# IPNS_v0_1_MCU.net
KiCad netlist of a schematic drawn in EAGLE
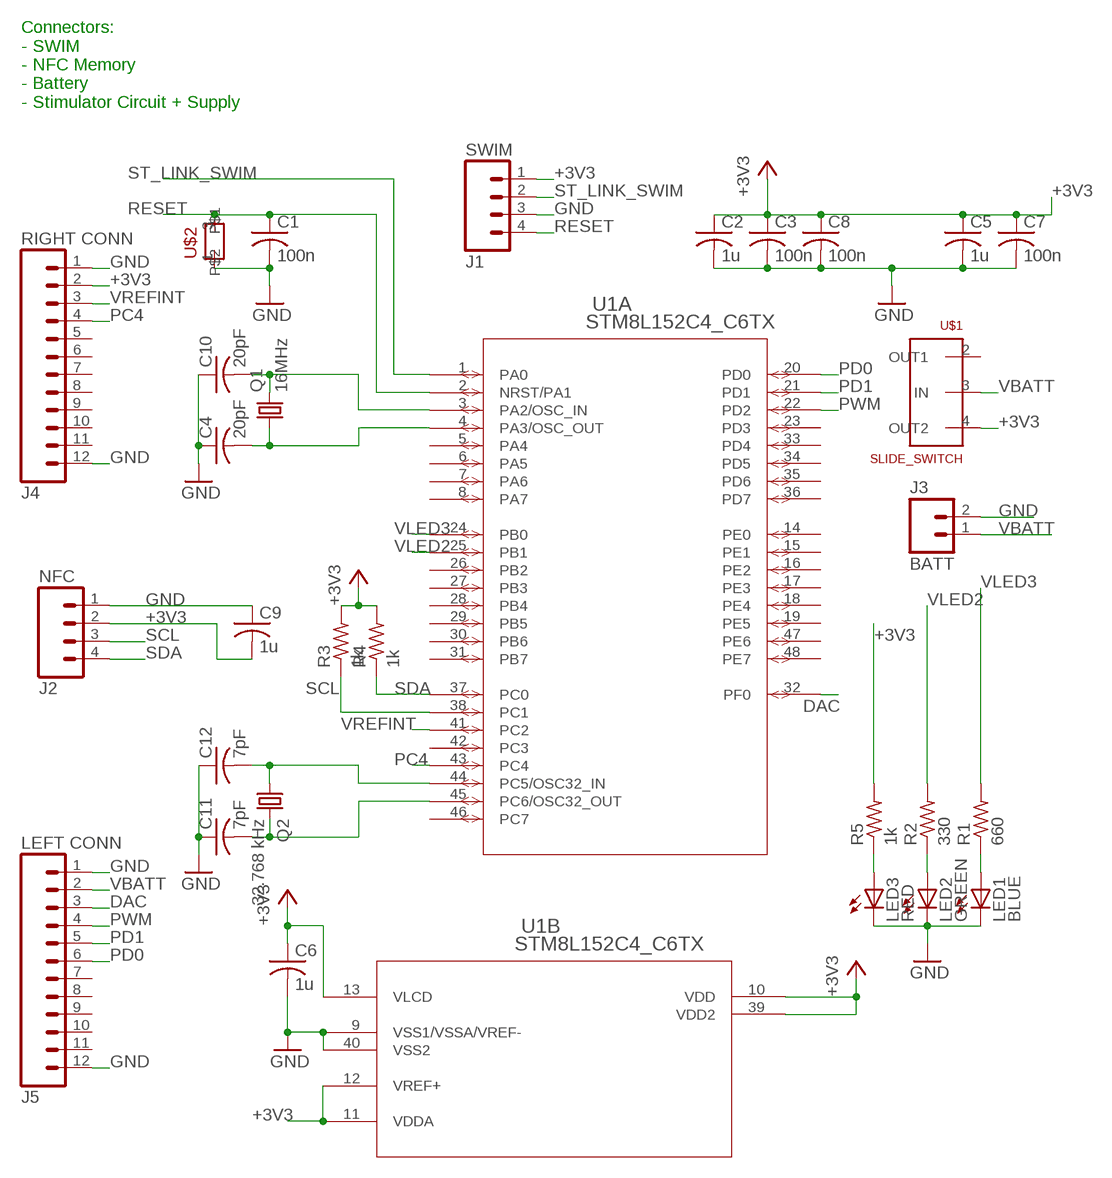
[diagram p0: schematic, sheet 1]

(export (version "E")
  (design (tool "Eeschema 10.0.6"))
  (components
    (comp (ref "C1")
      (value "100n")
      (footprint "eagle-import:C0805")
      (libsource (lib "eagle-import") (part "C-USC0805"))
    )
    (comp (ref "C2")
      (value "1u")
      (footprint "eagle-import:C0805")
      (libsource (lib "eagle-import") (part "C-USC0805"))
    )
    (comp (ref "C3")
      (value "100n")
      (footprint "eagle-import:C0805")
      (libsource (lib "eagle-import") (part "C-USC0805"))
    )
    (comp (ref "C4")
      (value "20pF")
      (footprint "eagle-import:C0805")
      (libsource (lib "eagle-import") (part "C-USC0805"))
    )
    (comp (ref "C5")
      (value "1u")
      (footprint "eagle-import:C0805")
      (libsource (lib "eagle-import") (part "C-USC0805"))
    )
    (comp (ref "C6")
      (value "1u")
      (footprint "eagle-import:C0805")
      (libsource (lib "eagle-import") (part "C-USC0805"))
    )
    (comp (ref "C7")
      (value "100n")
      (footprint "eagle-import:C0805")
      (libsource (lib "eagle-import") (part "C-USC0805"))
    )
    (comp (ref "C8")
      (value "100n")
      (footprint "eagle-import:C0805")
      (libsource (lib "eagle-import") (part "C-USC0805"))
    )
    (comp (ref "C9")
      (value "1u")
      (footprint "eagle-import:C0805")
      (libsource (lib "eagle-import") (part "C-USC0805"))
    )
    (comp (ref "C10")
      (value "20pF")
      (footprint "eagle-import:C0805")
      (libsource (lib "eagle-import") (part "C-USC0805"))
    )
    (comp (ref "C11")
      (value "7pF")
      (footprint "eagle-import:C0805")
      (libsource (lib "eagle-import") (part "C-USC0805"))
    )
    (comp (ref "C12")
      (value "7pF")
      (footprint "eagle-import:C0805")
      (libsource (lib "eagle-import") (part "C-USC0805"))
    )
    (comp (ref "J1")
      (value "SWIM")
      (footprint "eagle-import:1X04")
      (libsource (lib "eagle-import") (part "M04PTH"))
    )
    (comp (ref "J2")
      (value "NFC")
      (footprint "eagle-import:1X04")
      (libsource (lib "eagle-import") (part "M04PTH"))
    )
    (comp (ref "J3")
      (value "BATT")
      (footprint "eagle-import:1X02")
      (libsource (lib "eagle-import") (part "M02PTH"))
    )
    (comp (ref "J4")
      (value "RIGHT CONN")
      (footprint "eagle-import:1X12")
      (libsource (lib "eagle-import") (part "M12PTH"))
    )
    (comp (ref "J5")
      (value "LEFT CONN")
      (footprint "eagle-import:1X12")
      (libsource (lib "eagle-import") (part "M12PTH"))
    )
    (comp (ref "LED1")
      (value "BLUE")
      (footprint "eagle-import:CHIP-LED0805")
      (libsource (lib "eagle-import") (part "LEDCHIP-LED0805"))
    )
    (comp (ref "LED2")
      (value "GREEN")
      (footprint "eagle-import:CHIP-LED0805")
      (libsource (lib "eagle-import") (part "LEDCHIP-LED0805"))
    )
    (comp (ref "LED3")
      (value "RED")
      (footprint "eagle-import:CHIP-LED0805")
      (libsource (lib "eagle-import") (part "LEDCHIP-LED0805"))
    )
    (comp (ref "Q1")
      (value "16MHz")
      (footprint "eagle-import:HC49_S")
      (libsource (lib "eagle-import") (part "CRYSTALHC49S"))
    )
    (comp (ref "Q2")
      (value "32.768 kHz")
      (footprint "eagle-import:TC26H")
      (libsource (lib "eagle-import") (part "CRYSTALTC26H"))
    )
    (comp (ref "R1")
      (value "660")
      (footprint "eagle-import:R0805")
      (libsource (lib "eagle-import") (part "R-US_R0805"))
    )
    (comp (ref "R2")
      (value "330")
      (footprint "eagle-import:R0805")
      (libsource (lib "eagle-import") (part "R-US_R0805"))
    )
    (comp (ref "R3")
      (value "1k")
      (footprint "eagle-import:R0805")
      (libsource (lib "eagle-import") (part "R-US_R0805"))
    )
    (comp (ref "R4")
      (value "1k")
      (footprint "eagle-import:R0805")
      (libsource (lib "eagle-import") (part "R-US_R0805"))
    )
    (comp (ref "R5")
      (value "1k")
      (footprint "eagle-import:R0805")
      (libsource (lib "eagle-import") (part "R-US_R0805"))
    )
    (comp (ref "U$1")
      (value "SLIDE_SWITCH")
      (footprint "eagle-import:SLIDE_SWITCH")
      (libsource (lib "eagle-import") (part "SLIDE_SWITCH"))
    )
    (comp (ref "U$2")
      (value "PUSH-BUTTON")
      (footprint "eagle-import:PUSH-BUTTON")
      (libsource (lib "eagle-import") (part "PUSH-BUTTON"))
    )
    (comp (ref "U1")
      (value "STM8L152C4_C6TX")
      (footprint "eagle-import:LQFP48-7X7MM")
      (fields
        (field (name "MANUFACTURER_PART_NUMBER") "stm8l152c4_c6tx")
        (field (name "COPYRIGHT") "Copyright (C) 2016 Accelerated Designs. All rights reserved")
      )
      (libsource (lib "eagle-import") (part "STM8L152C4_C6TX"))
    )
  )
  (nets
    (net (code "1") (name "+3V3") (class "Default")
      (node (ref "C2") (pin "1") (pinfunction "1_1") (pintype "passive"))
      (node (ref "C3") (pin "1") (pinfunction "1_1") (pintype "passive"))
      (node (ref "C5") (pin "1") (pinfunction "1_1") (pintype "passive"))
      (node (ref "C6") (pin "1") (pinfunction "1_1") (pintype "passive"))
      (node (ref "C7") (pin "1") (pinfunction "1_1") (pintype "passive"))
      (node (ref "C8") (pin "1") (pinfunction "1_1") (pintype "passive"))
      (node (ref "C9") (pin "2") (pinfunction "2_2") (pintype "passive"))
      (node (ref "J1") (pin "1") (pinfunction "1_1") (pintype "passive"))
      (node (ref "J2") (pin "2") (pinfunction "2_2") (pintype "passive"))
      (node (ref "J4") (pin "2") (pinfunction "2_2") (pintype "passive"))
      (node (ref "R3") (pin "2") (pinfunction "2_2") (pintype "passive"))
      (node (ref "R4") (pin "2") (pinfunction "2_2") (pintype "passive"))
      (node (ref "R5") (pin "2") (pinfunction "2_2") (pintype "passive"))
      (node (ref "U$1") (pin "4") (pinfunction "OUT2_4") (pintype "bidirectional"))
      (node (ref "U1") (pin "10") (pinfunction "VDD_10") (pintype "power_in"))
      (node (ref "U1") (pin "11") (pinfunction "VDDA_11") (pintype "power_in"))
      (node (ref "U1") (pin "12") (pinfunction "VREF+_12") (pintype "power_in"))
      (node (ref "U1") (pin "13") (pinfunction "VLCD_13") (pintype "power_in"))
      (node (ref "U1") (pin "39") (pinfunction "VDD2_39") (pintype "power_in"))
    )
    (net (code "2") (name "/DAC") (class "Default")
      (node (ref "J5") (pin "3") (pinfunction "3_3") (pintype "passive"))
      (node (ref "U1") (pin "32") (pinfunction "PF0_32") (pintype "bidirectional"))
    )
    (net (code "3") (name "/PC4") (class "Default")
      (node (ref "J4") (pin "4") (pinfunction "4_4") (pintype "passive"))
      (node (ref "U1") (pin "43") (pinfunction "PC4_43") (pintype "bidirectional"))
    )
    (net (code "4") (name "/PD0") (class "Default")
      (node (ref "J5") (pin "6") (pinfunction "6_6") (pintype "passive"))
      (node (ref "U1") (pin "20") (pinfunction "PD0_20") (pintype "bidirectional"))
    )
    (net (code "5") (name "/PD1") (class "Default")
      (node (ref "J5") (pin "5") (pinfunction "5_5") (pintype "passive"))
      (node (ref "U1") (pin "21") (pinfunction "PD1_21") (pintype "bidirectional"))
    )
    (net (code "6") (name "/PWM") (class "Default")
      (node (ref "J5") (pin "4") (pinfunction "4_4") (pintype "passive"))
      (node (ref "U1") (pin "22") (pinfunction "PD2_22") (pintype "bidirectional"))
    )
    (net (code "7") (name "/RESET") (class "Default")
      (node (ref "C1") (pin "1") (pinfunction "1_1") (pintype "passive"))
      (node (ref "J1") (pin "4") (pinfunction "4_4") (pintype "passive"))
      (node (ref "U$2") (pin "3") (pinfunction "P$2_3") (pintype "bidirectional"))
      (node (ref "U1") (pin "2") (pinfunction "NRST/PA1_2") (pintype "bidirectional"))
    )
    (net (code "8") (name "/SCL") (class "Default")
      (node (ref "J2") (pin "3") (pinfunction "3_3") (pintype "passive"))
      (node (ref "R3") (pin "1") (pinfunction "1_1") (pintype "passive"))
      (node (ref "U1") (pin "38") (pinfunction "PC1_38") (pintype "bidirectional"))
    )
    (net (code "9") (name "/SDA") (class "Default")
      (node (ref "J2") (pin "4") (pinfunction "4_4") (pintype "passive"))
      (node (ref "R4") (pin "1") (pinfunction "1_1") (pintype "passive"))
      (node (ref "U1") (pin "37") (pinfunction "PC0_37") (pintype "bidirectional"))
    )
    (net (code "10") (name "/ST_LINK_SWIM") (class "Default")
      (node (ref "J1") (pin "2") (pinfunction "2_2") (pintype "passive"))
      (node (ref "U1") (pin "1") (pinfunction "PA0_1") (pintype "bidirectional"))
    )
    (net (code "11") (name "/VBATT") (class "Default")
      (node (ref "J3") (pin "1") (pinfunction "1_1") (pintype "passive"))
      (node (ref "J5") (pin "2") (pinfunction "2_2") (pintype "passive"))
      (node (ref "U$1") (pin "3") (pinfunction "IN_3") (pintype "bidirectional"))
    )
    (net (code "12") (name "/VLED2") (class "Default")
      (node (ref "R2") (pin "2") (pinfunction "2_2") (pintype "passive"))
      (node (ref "U1") (pin "25") (pinfunction "PB1_25") (pintype "bidirectional"))
    )
    (net (code "13") (name "/VLED3") (class "Default")
      (node (ref "R1") (pin "2") (pinfunction "2_2") (pintype "passive"))
      (node (ref "U1") (pin "24") (pinfunction "PB0_24") (pintype "bidirectional"))
    )
    (net (code "14") (name "/VREFINT") (class "Default")
      (node (ref "J4") (pin "3") (pinfunction "3_3") (pintype "passive"))
      (node (ref "U1") (pin "41") (pinfunction "PC2_41") (pintype "bidirectional"))
    )
    (net (code "15") (name "GND") (class "Default")
      (node (ref "C1") (pin "2") (pinfunction "2_2") (pintype "passive"))
      (node (ref "C10") (pin "1") (pinfunction "1_1") (pintype "passive"))
      (node (ref "C11") (pin "1") (pinfunction "1_1") (pintype "passive"))
      (node (ref "C12") (pin "1") (pinfunction "1_1") (pintype "passive"))
      (node (ref "C2") (pin "2") (pinfunction "2_2") (pintype "passive"))
      (node (ref "C3") (pin "2") (pinfunction "2_2") (pintype "passive"))
      (node (ref "C4") (pin "1") (pinfunction "1_1") (pintype "passive"))
      (node (ref "C5") (pin "2") (pinfunction "2_2") (pintype "passive"))
      (node (ref "C6") (pin "2") (pinfunction "2_2") (pintype "passive"))
      (node (ref "C7") (pin "2") (pinfunction "2_2") (pintype "passive"))
      (node (ref "C8") (pin "2") (pinfunction "2_2") (pintype "passive"))
      (node (ref "C9") (pin "1") (pinfunction "1_1") (pintype "passive"))
      (node (ref "J1") (pin "3") (pinfunction "3_3") (pintype "passive"))
      (node (ref "J2") (pin "1") (pinfunction "1_1") (pintype "passive"))
      (node (ref "J3") (pin "2") (pinfunction "2_2") (pintype "passive"))
      (node (ref "J4") (pin "1") (pinfunction "1_1") (pintype "passive"))
      (node (ref "J4") (pin "12") (pinfunction "12_12") (pintype "passive"))
      (node (ref "J5") (pin "1") (pinfunction "1_1") (pintype "passive"))
      (node (ref "J5") (pin "12") (pinfunction "12_12") (pintype "passive"))
      (node (ref "LED1") (pin "C") (pinfunction "C_C") (pintype "passive"))
      (node (ref "LED2") (pin "C") (pinfunction "C_C") (pintype "passive"))
      (node (ref "LED3") (pin "C") (pinfunction "C_C") (pintype "passive"))
      (node (ref "U$2") (pin "1") (pinfunction "P$1_1") (pintype "bidirectional"))
      (node (ref "U1") (pin "40") (pinfunction "VSS2_40") (pintype "power_in"))
      (node (ref "U1") (pin "9") (pinfunction "VSS1/VSSA/VREF-_9") (pintype "power_in"))
    )
    (net (code "16") (name "Net-(LED1-PadA)") (class "Default")
      (node (ref "LED1") (pin "A") (pinfunction "A_A") (pintype "passive"))
      (node (ref "R1") (pin "1") (pinfunction "1_1") (pintype "passive"))
    )
    (net (code "17") (name "Net-(LED2-PadA)") (class "Default")
      (node (ref "LED2") (pin "A") (pinfunction "A_A") (pintype "passive"))
      (node (ref "R2") (pin "1") (pinfunction "1_1") (pintype "passive"))
    )
    (net (code "18") (name "Net-(LED3-PadA)") (class "Default")
      (node (ref "LED3") (pin "A") (pinfunction "A_A") (pintype "passive"))
      (node (ref "R5") (pin "1") (pinfunction "1_1") (pintype "passive"))
    )
    (net (code "19") (name "Net-(U1A-PA2{slash}OSC_IN)") (class "Default")
      (node (ref "C10") (pin "2") (pinfunction "2_2") (pintype "passive"))
      (node (ref "Q1") (pin "2") (pinfunction "2_2") (pintype "passive"))
      (node (ref "U1") (pin "3") (pinfunction "PA2/OSC_IN_3") (pintype "bidirectional"))
    )
    (net (code "20") (name "Net-(U1A-PA3{slash}OSC_OUT)") (class "Default")
      (node (ref "C4") (pin "2") (pinfunction "2_2") (pintype "passive"))
      (node (ref "Q1") (pin "1") (pinfunction "1_1") (pintype "passive"))
      (node (ref "U1") (pin "4") (pinfunction "PA3/OSC_OUT_4") (pintype "bidirectional"))
    )
    (net (code "21") (name "Net-(U1A-PC5{slash}OSC32_IN)") (class "Default")
      (node (ref "C12") (pin "2") (pinfunction "2_2") (pintype "passive"))
      (node (ref "Q2") (pin "1") (pinfunction "1_1") (pintype "passive"))
      (node (ref "U1") (pin "44") (pinfunction "PC5/OSC32_IN_44") (pintype "bidirectional"))
    )
    (net (code "22") (name "Net-(U1A-PC6{slash}OSC32_OUT)") (class "Default")
      (node (ref "C11") (pin "2") (pinfunction "2_2") (pintype "passive"))
      (node (ref "Q2") (pin "2") (pinfunction "2_2") (pintype "passive"))
      (node (ref "U1") (pin "45") (pinfunction "PC6/OSC32_OUT_45") (pintype "bidirectional"))
    )
    (net (code "23") (name "unconnected-(J4-Pad5)") (class "Default")
      (node (ref "J4") (pin "5") (pinfunction "5_5") (pintype "passive"))
    )
    (net (code "24") (name "unconnected-(J4-Pad6)") (class "Default")
      (node (ref "J4") (pin "6") (pinfunction "6_6") (pintype "passive"))
    )
    (net (code "25") (name "unconnected-(J4-Pad7)") (class "Default")
      (node (ref "J4") (pin "7") (pinfunction "7_7") (pintype "passive"))
    )
    (net (code "26") (name "unconnected-(J4-Pad8)") (class "Default")
      (node (ref "J4") (pin "8") (pinfunction "8_8") (pintype "passive"))
    )
    (net (code "27") (name "unconnected-(J4-Pad9)") (class "Default")
      (node (ref "J4") (pin "9") (pinfunction "9_9") (pintype "passive"))
    )
    (net (code "28") (name "unconnected-(J4-Pad10)") (class "Default")
      (node (ref "J4") (pin "10") (pinfunction "10_10") (pintype "passive"))
    )
    (net (code "29") (name "unconnected-(J4-Pad11)") (class "Default")
      (node (ref "J4") (pin "11") (pinfunction "11_11") (pintype "passive"))
    )
    (net (code "30") (name "unconnected-(J5-Pad7)") (class "Default")
      (node (ref "J5") (pin "7") (pinfunction "7_7") (pintype "passive"))
    )
    (net (code "31") (name "unconnected-(J5-Pad8)") (class "Default")
      (node (ref "J5") (pin "8") (pinfunction "8_8") (pintype "passive"))
    )
    (net (code "32") (name "unconnected-(J5-Pad9)") (class "Default")
      (node (ref "J5") (pin "9") (pinfunction "9_9") (pintype "passive"))
    )
    (net (code "33") (name "unconnected-(J5-Pad10)") (class "Default")
      (node (ref "J5") (pin "10") (pinfunction "10_10") (pintype "passive"))
    )
    (net (code "34") (name "unconnected-(J5-Pad11)") (class "Default")
      (node (ref "J5") (pin "11") (pinfunction "11_11") (pintype "passive"))
    )
    (net (code "35") (name "unconnected-(U$1-OUT1-Pad2)") (class "Default")
      (node (ref "U$1") (pin "2") (pinfunction "OUT1_2") (pintype "bidirectional"))
    )
    (net (code "36") (name "unconnected-(U1A-PA4-Pad5)") (class "Default")
      (node (ref "U1") (pin "5") (pinfunction "PA4_5") (pintype "bidirectional"))
    )
    (net (code "37") (name "unconnected-(U1A-PA5-Pad6)") (class "Default")
      (node (ref "U1") (pin "6") (pinfunction "PA5_6") (pintype "bidirectional"))
    )
    (net (code "38") (name "unconnected-(U1A-PA6-Pad7)") (class "Default")
      (node (ref "U1") (pin "7") (pinfunction "PA6_7") (pintype "bidirectional"))
    )
    (net (code "39") (name "unconnected-(U1A-PA7-Pad8)") (class "Default")
      (node (ref "U1") (pin "8") (pinfunction "PA7_8") (pintype "bidirectional"))
    )
    (net (code "40") (name "unconnected-(U1A-PB2-Pad26)") (class "Default")
      (node (ref "U1") (pin "26") (pinfunction "PB2_26") (pintype "bidirectional"))
    )
    (net (code "41") (name "unconnected-(U1A-PB3-Pad27)") (class "Default")
      (node (ref "U1") (pin "27") (pinfunction "PB3_27") (pintype "bidirectional"))
    )
    (net (code "42") (name "unconnected-(U1A-PB4-Pad28)") (class "Default")
      (node (ref "U1") (pin "28") (pinfunction "PB4_28") (pintype "bidirectional"))
    )
    (net (code "43") (name "unconnected-(U1A-PB5-Pad29)") (class "Default")
      (node (ref "U1") (pin "29") (pinfunction "PB5_29") (pintype "bidirectional"))
    )
    (net (code "44") (name "unconnected-(U1A-PB6-Pad30)") (class "Default")
      (node (ref "U1") (pin "30") (pinfunction "PB6_30") (pintype "bidirectional"))
    )
    (net (code "45") (name "unconnected-(U1A-PB7-Pad31)") (class "Default")
      (node (ref "U1") (pin "31") (pinfunction "PB7_31") (pintype "bidirectional"))
    )
    (net (code "46") (name "unconnected-(U1A-PC3-Pad42)") (class "Default")
      (node (ref "U1") (pin "42") (pinfunction "PC3_42") (pintype "bidirectional"))
    )
    (net (code "47") (name "unconnected-(U1A-PC7-Pad46)") (class "Default")
      (node (ref "U1") (pin "46") (pinfunction "PC7_46") (pintype "bidirectional"))
    )
    (net (code "48") (name "unconnected-(U1A-PD3-Pad23)") (class "Default")
      (node (ref "U1") (pin "23") (pinfunction "PD3_23") (pintype "bidirectional"))
    )
    (net (code "49") (name "unconnected-(U1A-PD4-Pad33)") (class "Default")
      (node (ref "U1") (pin "33") (pinfunction "PD4_33") (pintype "bidirectional"))
    )
    (net (code "50") (name "unconnected-(U1A-PD5-Pad34)") (class "Default")
      (node (ref "U1") (pin "34") (pinfunction "PD5_34") (pintype "bidirectional"))
    )
    (net (code "51") (name "unconnected-(U1A-PD6-Pad35)") (class "Default")
      (node (ref "U1") (pin "35") (pinfunction "PD6_35") (pintype "bidirectional"))
    )
    (net (code "52") (name "unconnected-(U1A-PD7-Pad36)") (class "Default")
      (node (ref "U1") (pin "36") (pinfunction "PD7_36") (pintype "bidirectional"))
    )
    (net (code "53") (name "unconnected-(U1A-PE0-Pad14)") (class "Default")
      (node (ref "U1") (pin "14") (pinfunction "PE0_14") (pintype "bidirectional"))
    )
    (net (code "54") (name "unconnected-(U1A-PE1-Pad15)") (class "Default")
      (node (ref "U1") (pin "15") (pinfunction "PE1_15") (pintype "bidirectional"))
    )
    (net (code "55") (name "unconnected-(U1A-PE2-Pad16)") (class "Default")
      (node (ref "U1") (pin "16") (pinfunction "PE2_16") (pintype "bidirectional"))
    )
    (net (code "56") (name "unconnected-(U1A-PE3-Pad17)") (class "Default")
      (node (ref "U1") (pin "17") (pinfunction "PE3_17") (pintype "bidirectional"))
    )
    (net (code "57") (name "unconnected-(U1A-PE4-Pad18)") (class "Default")
      (node (ref "U1") (pin "18") (pinfunction "PE4_18") (pintype "bidirectional"))
    )
    (net (code "58") (name "unconnected-(U1A-PE5-Pad19)") (class "Default")
      (node (ref "U1") (pin "19") (pinfunction "PE5_19") (pintype "bidirectional"))
    )
    (net (code "59") (name "unconnected-(U1A-PE6-Pad47)") (class "Default")
      (node (ref "U1") (pin "47") (pinfunction "PE6_47") (pintype "bidirectional"))
    )
    (net (code "60") (name "unconnected-(U1A-PE7-Pad48)") (class "Default")
      (node (ref "U1") (pin "48") (pinfunction "PE7_48") (pintype "bidirectional"))
    )
  )
)
